# Blinds_Stepper.net
KiCad netlist of a schematic drawn in EAGLE
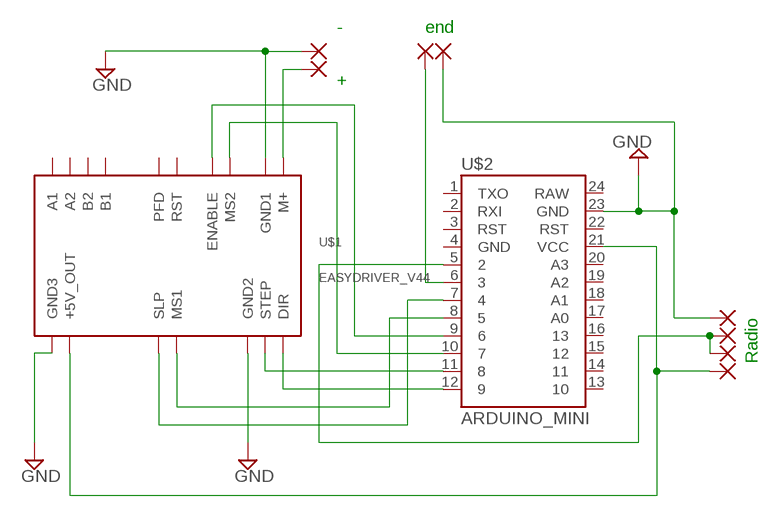
[diagram p0: schematic, sheet 1]

(export (version "E")
  (design (tool "Eeschema 10.0.6"))
  (components
    (comp (ref "E1")
      (value "1,6/0,8")
      (footprint "eagle-import:1,6_0,8")
      (libsource (lib "eagle-import") (part "1,6/0,8"))
    )
    (comp (ref "E2")
      (value "1,6/0,8")
      (footprint "eagle-import:1,6_0,8")
      (libsource (lib "eagle-import") (part "1,6/0,8"))
    )
    (comp (ref "M-")
      (value "1,6/0,8")
      (footprint "eagle-import:1,6_0,8")
      (libsource (lib "eagle-import") (part "1,6/0,8"))
    )
    (comp (ref "R+")
      (value "1,6/0,8")
      (footprint "eagle-import:1,6_0,8")
      (libsource (lib "eagle-import") (part "1,6/0,8"))
    )
    (comp (ref "R-")
      (value "1,6/0,8")
      (footprint "eagle-import:1,6_0,8")
      (libsource (lib "eagle-import") (part "1,6/0,8"))
    )
    (comp (ref "R1")
      (value "1,6/0,8")
      (footprint "eagle-import:1,6_0,8")
      (libsource (lib "eagle-import") (part "1,6/0,8"))
    )
    (comp (ref "R2")
      (value "1,6/0,8")
      (footprint "eagle-import:1,6_0,8")
      (libsource (lib "eagle-import") (part "1,6/0,8"))
    )
    (comp (ref "U$1")
      (value "EASYDRIVER_V44")
      (footprint "eagle-import:EASYDRIVER_V44")
      (libsource (lib "eagle-import") (part "EASYDRIVER_V44"))
    )
    (comp (ref "U$2")
      (value "ARDUINO_MINI")
      (footprint "eagle-import:ARDUINO_MINI")
      (libsource (lib "eagle-import") (part "ARDUINO_MINI"))
    )
    (comp (ref "X")
      (value "1,6/0,8")
      (footprint "eagle-import:1,6_0,8")
      (libsource (lib "eagle-import") (part "1,6/0,8"))
    )
  )
  (nets
    (net (code "1") (name "GND") (class "Default")
      (node (ref "E2") (pin "1") (pinfunction "P_1") (pintype "passive"))
      (node (ref "M-") (pin "1") (pinfunction "P_1") (pintype "passive"))
      (node (ref "R-") (pin "1") (pinfunction "P_1") (pintype "passive"))
      (node (ref "U$1") (pin "GND1") (pinfunction "GND1_GND1") (pintype "bidirectional"))
      (node (ref "U$1") (pin "GND2") (pinfunction "GND2_GND2") (pintype "bidirectional"))
      (node (ref "U$1") (pin "GND3") (pinfunction "GND3_GND3") (pintype "bidirectional"))
      (node (ref "U$2") (pin "23") (pinfunction "GND_23") (pintype "bidirectional"))
    )
    (net (code "2") (name "Net-(E1-P)") (class "Default")
      (node (ref "E1") (pin "1") (pinfunction "P_1") (pintype "passive"))
      (node (ref "U$2") (pin "6") (pinfunction "3_6") (pintype "bidirectional"))
    )
    (net (code "3") (name "Net-(R+-P)") (class "Default")
      (node (ref "R+") (pin "1") (pinfunction "P_1") (pintype "passive"))
      (node (ref "U$1") (pin "P$11") (pinfunction "+5V_OUT_P$11") (pintype "bidirectional"))
      (node (ref "U$2") (pin "21") (pinfunction "VCC_21") (pintype "bidirectional"))
    )
    (net (code "4") (name "Net-(R1-P)") (class "Default")
      (node (ref "R1") (pin "1") (pinfunction "P_1") (pintype "passive"))
      (node (ref "R2") (pin "1") (pinfunction "P_1") (pintype "passive"))
      (node (ref "U$2") (pin "5") (pinfunction "2_5") (pintype "bidirectional"))
    )
    (net (code "5") (name "Net-(U$1-SLP)") (class "Default")
      (node (ref "U$1") (pin "SLEEP") (pinfunction "SLP_SLEEP") (pintype "bidirectional"))
      (node (ref "U$2") (pin "7") (pinfunction "4_7") (pintype "bidirectional"))
    )
    (net (code "6") (name "Net-(U$2-5)") (class "Default")
      (node (ref "U$1") (pin "MS1") (pinfunction "MS1_MS1") (pintype "bidirectional"))
      (node (ref "U$2") (pin "8") (pinfunction "5_8") (pintype "bidirectional"))
    )
    (net (code "7") (name "Net-(U$2-6)") (class "Default")
      (node (ref "U$1") (pin "ENABLE") (pinfunction "ENABLE_ENABLE") (pintype "bidirectional"))
      (node (ref "U$2") (pin "9") (pinfunction "6_9") (pintype "bidirectional"))
    )
    (net (code "8") (name "Net-(U$2-7)") (class "Default")
      (node (ref "U$1") (pin "MS2") (pinfunction "MS2_MS2") (pintype "bidirectional"))
      (node (ref "U$2") (pin "10") (pinfunction "7_10") (pintype "bidirectional"))
    )
    (net (code "9") (name "Net-(U$2-8)") (class "Default")
      (node (ref "U$1") (pin "STEP") (pinfunction "STEP_STEP") (pintype "bidirectional"))
      (node (ref "U$2") (pin "11") (pinfunction "8_11") (pintype "bidirectional"))
    )
    (net (code "10") (name "Net-(U$2-9)") (class "Default")
      (node (ref "U$1") (pin "DIR") (pinfunction "DIR_DIR") (pintype "bidirectional"))
      (node (ref "U$2") (pin "12") (pinfunction "9_12") (pintype "bidirectional"))
    )
    (net (code "11") (name "Net-(X-P)") (class "Default")
      (node (ref "U$1") (pin "M+") (pinfunction "M+_M+") (pintype "bidirectional"))
      (node (ref "X") (pin "1") (pinfunction "P_1") (pintype "passive"))
    )
    (net (code "12") (name "unconnected-(U$1-PadA1)") (class "Default")
      (node (ref "U$1") (pin "A1") (pinfunction "A1_A1") (pintype "bidirectional"))
    )
    (net (code "13") (name "unconnected-(U$1-PadA2)") (class "Default")
      (node (ref "U$1") (pin "A2") (pinfunction "A2_A2") (pintype "bidirectional"))
    )
    (net (code "14") (name "unconnected-(U$1-PadB1)") (class "Default")
      (node (ref "U$1") (pin "B1") (pinfunction "B1_B1") (pintype "bidirectional"))
    )
    (net (code "15") (name "unconnected-(U$1-PadB2)") (class "Default")
      (node (ref "U$1") (pin "B2") (pinfunction "B2_B2") (pintype "bidirectional"))
    )
    (net (code "16") (name "unconnected-(U$1-PadPFD)") (class "Default")
      (node (ref "U$1") (pin "PFD") (pinfunction "PFD_PFD") (pintype "bidirectional"))
    )
    (net (code "17") (name "unconnected-(U$1-PadRST)") (class "Default")
      (node (ref "U$1") (pin "RST") (pinfunction "RST_RST") (pintype "bidirectional"))
    )
    (net (code "18") (name "unconnected-(U$2-10-Pad13)") (class "Default")
      (node (ref "U$2") (pin "13") (pinfunction "10_13") (pintype "bidirectional"))
    )
    (net (code "19") (name "unconnected-(U$2-11-Pad14)") (class "Default")
      (node (ref "U$2") (pin "14") (pinfunction "11_14") (pintype "bidirectional"))
    )
    (net (code "20") (name "unconnected-(U$2-12-Pad15)") (class "Default")
      (node (ref "U$2") (pin "15") (pinfunction "12_15") (pintype "bidirectional"))
    )
    (net (code "21") (name "unconnected-(U$2-13-Pad16)") (class "Default")
      (node (ref "U$2") (pin "16") (pinfunction "13_16") (pintype "bidirectional"))
    )
    (net (code "22") (name "unconnected-(U$2-A0-Pad17)") (class "Default")
      (node (ref "U$2") (pin "17") (pinfunction "A0_17") (pintype "bidirectional"))
    )
    (net (code "23") (name "unconnected-(U$2-A1-Pad18)") (class "Default")
      (node (ref "U$2") (pin "18") (pinfunction "A1_18") (pintype "bidirectional"))
    )
    (net (code "24") (name "unconnected-(U$2-A2-Pad19)") (class "Default")
      (node (ref "U$2") (pin "19") (pinfunction "A2_19") (pintype "bidirectional"))
    )
    (net (code "25") (name "unconnected-(U$2-A3-Pad20)") (class "Default")
      (node (ref "U$2") (pin "20") (pinfunction "A3_20") (pintype "bidirectional"))
    )
    (net (code "26") (name "unconnected-(U$2-GND-Pad4)") (class "Default")
      (node (ref "U$2") (pin "4") (pinfunction "GND_4") (pintype "bidirectional"))
    )
    (net (code "27") (name "unconnected-(U$2-RAW-Pad24)") (class "Default")
      (node (ref "U$2") (pin "24") (pinfunction "RAW_24") (pintype "bidirectional"))
    )
    (net (code "28") (name "unconnected-(U$2-RST-Pad3)") (class "Default")
      (node (ref "U$2") (pin "3") (pinfunction "RST_3") (pintype "bidirectional"))
    )
    (net (code "29") (name "unconnected-(U$2-RST-Pad22)") (class "Default")
      (node (ref "U$2") (pin "22") (pinfunction "RST_22") (pintype "bidirectional"))
    )
    (net (code "30") (name "unconnected-(U$2-RXI-Pad2)") (class "Default")
      (node (ref "U$2") (pin "2") (pinfunction "RXI_2") (pintype "bidirectional"))
    )
    (net (code "31") (name "unconnected-(U$2-TXO-Pad1)") (class "Default")
      (node (ref "U$2") (pin "1") (pinfunction "TXO_1") (pintype "bidirectional"))
    )
  )
)
